# zeeSoC_mp3_Shield_v1_0.net
KiCad netlist of a schematic drawn in EAGLE
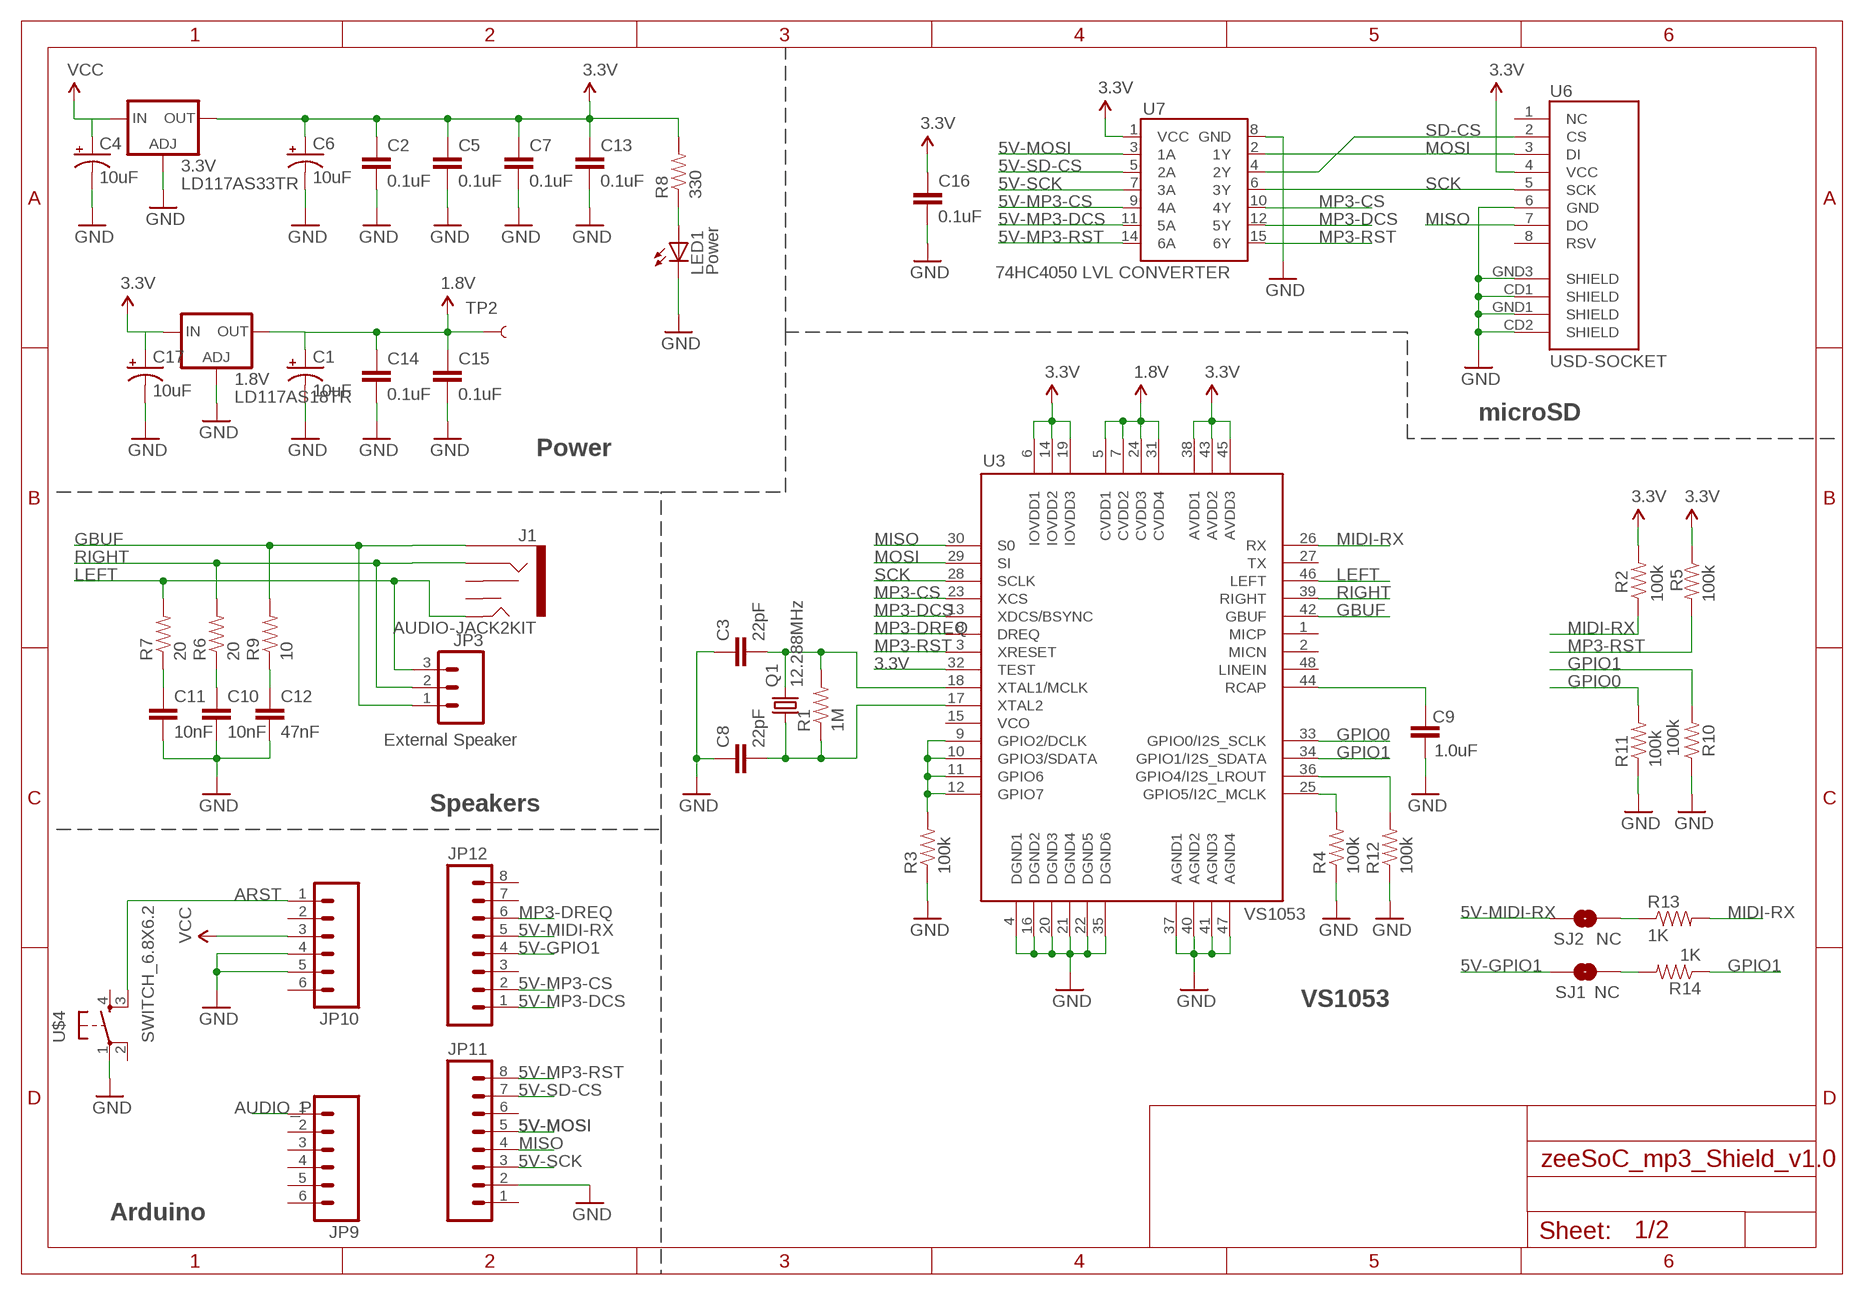
[diagram p0: schematic, sheet 1]
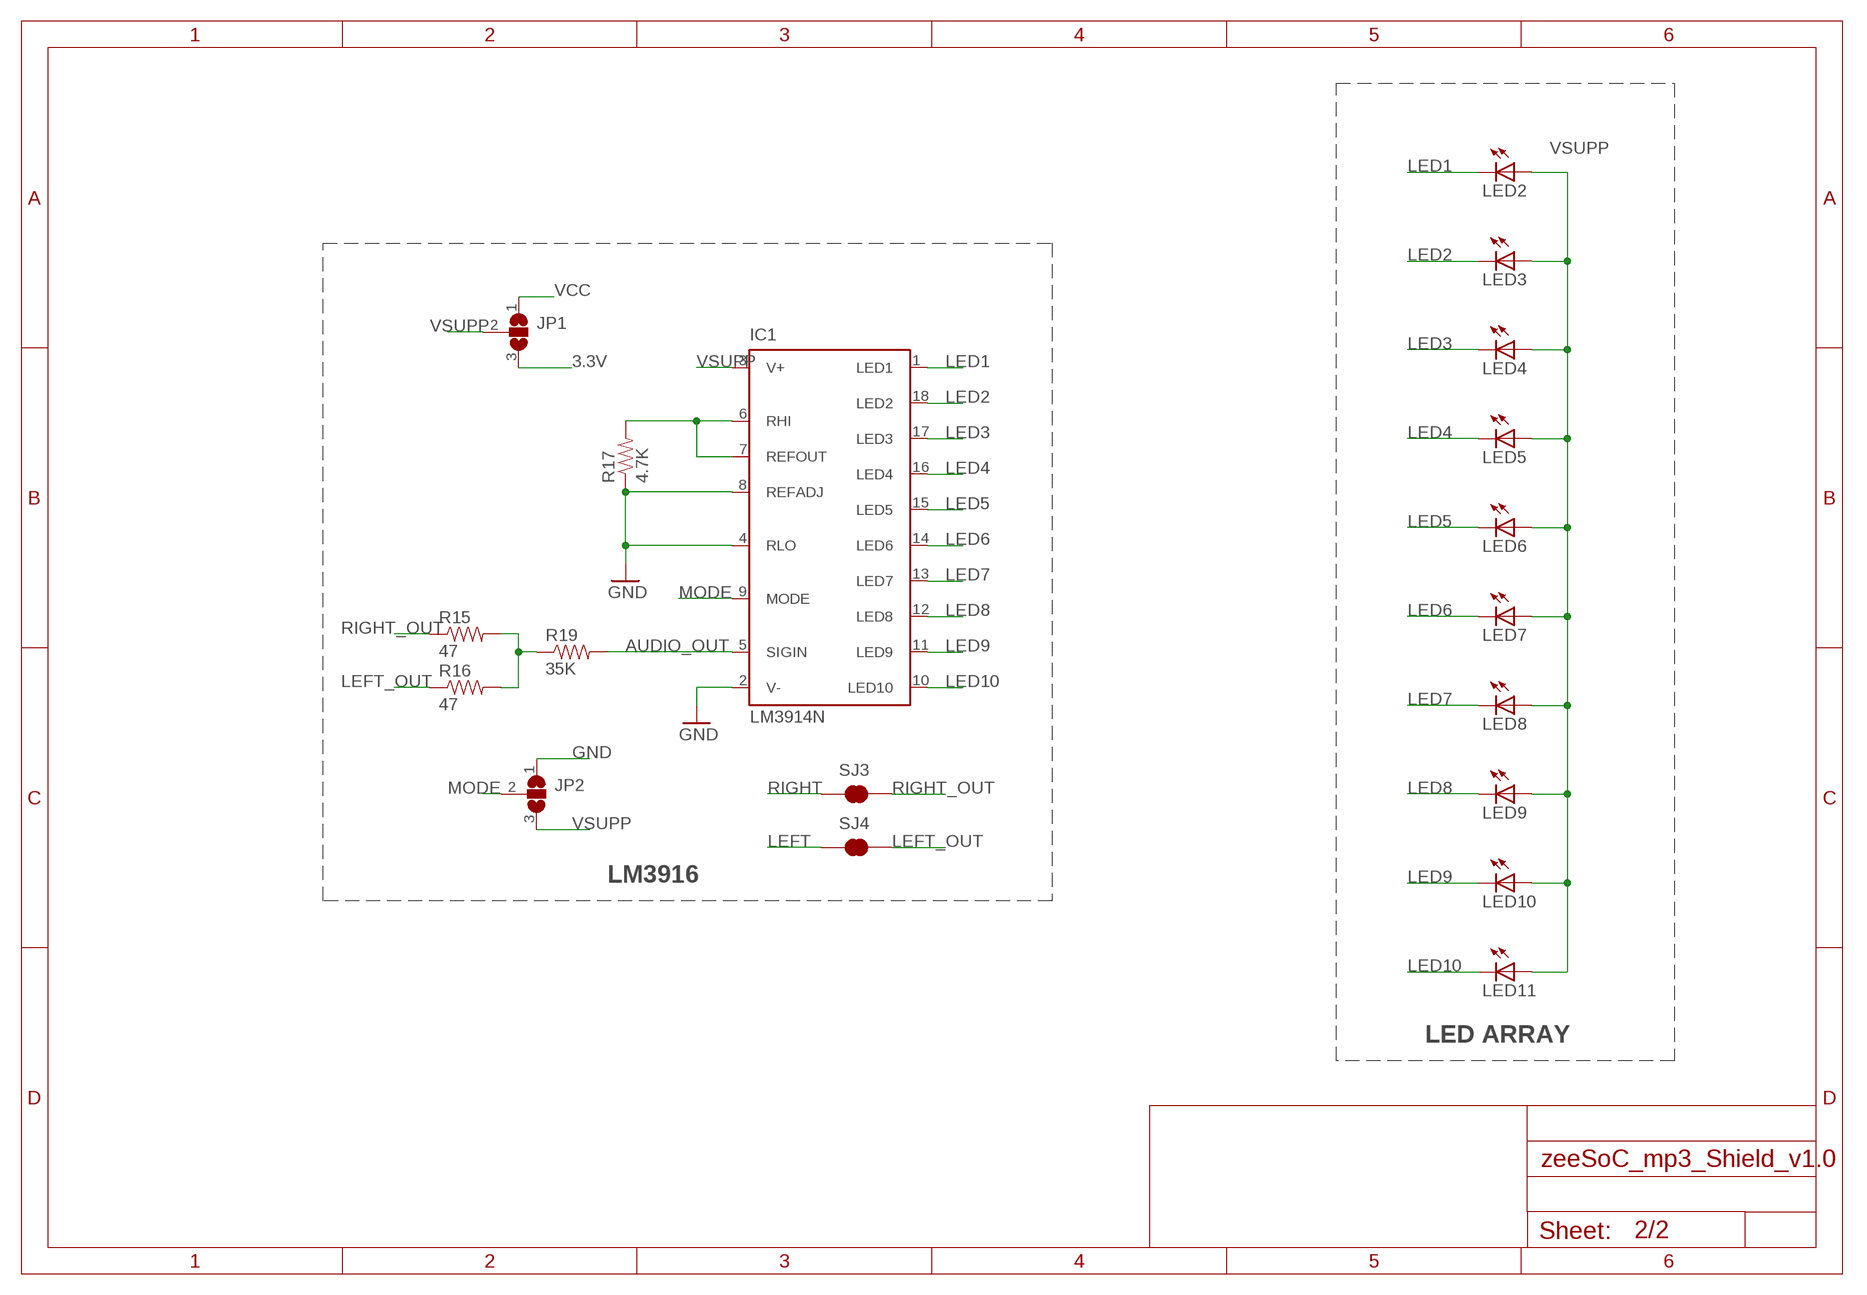
[diagram p1: schematic, sheet 2]

(export (version "E")
  (design (tool "Eeschema 10.0.6"))
  (components
    (comp (ref "1.8V")
      (value "LD117AS18TR")
      (footprint "eagle-import:SOT223")
      (libsource (lib "eagle-import") (part "LD117A?S18TR"))
    )
    (comp (ref "3.3V")
      (value "LD117AS33TR")
      (footprint "eagle-import:SOT223")
      (libsource (lib "eagle-import") (part "LD117A?S33TR"))
    )
    (comp (ref "C1")
      (value "10uF")
      (footprint "eagle-import:EIA3216")
      (libsource (lib "eagle-import") (part "CAP_POL1206"))
    )
    (comp (ref "C2")
      (value "0.1uF")
      (footprint "eagle-import:0603-CAP")
      (libsource (lib "eagle-import") (part "CAP0603-CAP"))
    )
    (comp (ref "C3")
      (value "22pF")
      (footprint "eagle-import:0603-CAP")
      (libsource (lib "eagle-import") (part "CAP0603-CAP"))
    )
    (comp (ref "C4")
      (value "10uF")
      (footprint "eagle-import:EIA3216")
      (libsource (lib "eagle-import") (part "CAP_POL1206"))
    )
    (comp (ref "C5")
      (value "0.1uF")
      (footprint "eagle-import:0603-CAP")
      (libsource (lib "eagle-import") (part "CAP0603-CAP"))
    )
    (comp (ref "C6")
      (value "10uF")
      (footprint "eagle-import:EIA3216")
      (libsource (lib "eagle-import") (part "CAP_POL1206"))
    )
    (comp (ref "C7")
      (value "0.1uF")
      (footprint "eagle-import:0603-CAP")
      (libsource (lib "eagle-import") (part "CAP0603-CAP"))
    )
    (comp (ref "C8")
      (value "22pF")
      (footprint "eagle-import:0603-CAP")
      (libsource (lib "eagle-import") (part "CAP0603-CAP"))
    )
    (comp (ref "C9")
      (value "1.0uF")
      (footprint "eagle-import:0603-CAP")
      (libsource (lib "eagle-import") (part "CAP0603-CAP"))
    )
    (comp (ref "C10")
      (value "10nF")
      (footprint "eagle-import:0603-CAP")
      (libsource (lib "eagle-import") (part "CAP0603-CAP"))
    )
    (comp (ref "C11")
      (value "10nF")
      (footprint "eagle-import:0603-CAP")
      (libsource (lib "eagle-import") (part "CAP0603-CAP"))
    )
    (comp (ref "C12")
      (value "47nF")
      (footprint "eagle-import:0603-CAP")
      (libsource (lib "eagle-import") (part "CAP0603-CAP"))
    )
    (comp (ref "C13")
      (value "0.1uF")
      (footprint "eagle-import:0603-CAP")
      (libsource (lib "eagle-import") (part "CAP0603-CAP"))
    )
    (comp (ref "C14")
      (value "0.1uF")
      (footprint "eagle-import:0603-CAP")
      (libsource (lib "eagle-import") (part "CAP0603-CAP"))
    )
    (comp (ref "C15")
      (value "0.1uF")
      (footprint "eagle-import:0603-CAP")
      (libsource (lib "eagle-import") (part "CAP0603-CAP"))
    )
    (comp (ref "C16")
      (value "0.1uF")
      (footprint "eagle-import:0603-CAP")
      (libsource (lib "eagle-import") (part "CAP0603-CAP"))
    )
    (comp (ref "C17")
      (value "10uF")
      (footprint "eagle-import:EIA3216")
      (libsource (lib "eagle-import") (part "CAP_POL1206"))
    )
    (comp (ref "J1")
      (value "AUDIO-JACK2KIT")
      (footprint "eagle-import:AUDIO-JACK-KIT")
      (libsource (lib "eagle-import") (part "AUDIO-JACK2KIT"))
    )
    (comp (ref "JP3")
      (value "External Speaker")
      (footprint "eagle-import:1X03")
      (libsource (lib "eagle-import") (part "M03PTH"))
    )
    (comp (ref "JP9")
      (value "M06SILK_FEMALE_PTH")
      (footprint "eagle-import:1X06")
      (libsource (lib "eagle-import") (part "M06SILK_FEMALE_PTH"))
    )
    (comp (ref "JP10")
      (value "M06SILK_FEMALE_PTH")
      (footprint "eagle-import:1X06")
      (libsource (lib "eagle-import") (part "M06SILK_FEMALE_PTH"))
    )
    (comp (ref "JP11")
      (value "M08SILK_FEMALE_PTH")
      (footprint "eagle-import:1X08")
      (libsource (lib "eagle-import") (part "M08SILK_FEMALE_PTH"))
    )
    (comp (ref "JP12")
      (value "M08SILK_FEMALE_PTH")
      (footprint "eagle-import:1X08")
      (libsource (lib "eagle-import") (part "M08SILK_FEMALE_PTH"))
    )
    (comp (ref "LED1")
      (value "Power")
      (footprint "eagle-import:LED-0603")
      (libsource (lib "eagle-import") (part "LED0603"))
    )
    (comp (ref "Q1")
      (value "12.288MHz")
      (footprint "eagle-import:HC49US")
      (libsource (lib "eagle-import") (part "CRYSTALHC49US"))
    )
    (comp (ref "R1")
      (value "1M")
      (footprint "eagle-import:0603-RES")
      (libsource (lib "eagle-import") (part "SparkFun-Resistors_RESISTOR0603-RES"))
    )
    (comp (ref "R2")
      (value "100k")
      (footprint "eagle-import:0603-RES")
      (libsource (lib "eagle-import") (part "SparkFun-Resistors_RESISTOR0603-RES"))
    )
    (comp (ref "R3")
      (value "100k")
      (footprint "eagle-import:0603-RES")
      (libsource (lib "eagle-import") (part "SparkFun-Resistors_RESISTOR0603-RES"))
    )
    (comp (ref "R4")
      (value "100k")
      (footprint "eagle-import:0603-RES")
      (libsource (lib "eagle-import") (part "SparkFun-Resistors_RESISTOR0603-RES"))
    )
    (comp (ref "R5")
      (value "100k")
      (footprint "eagle-import:0603-RES")
      (libsource (lib "eagle-import") (part "SparkFun-Resistors_RESISTOR0603-RES"))
    )
    (comp (ref "R6")
      (value "20")
      (footprint "eagle-import:0603-RES")
      (libsource (lib "eagle-import") (part "SparkFun-Resistors_RESISTOR0603-RES"))
    )
    (comp (ref "R7")
      (value "20")
      (footprint "eagle-import:0603-RES")
      (libsource (lib "eagle-import") (part "SparkFun-Resistors_RESISTOR0603-RES"))
    )
    (comp (ref "R8")
      (value "330")
      (footprint "eagle-import:0603-RES")
      (libsource (lib "eagle-import") (part "SparkFun-Resistors_RESISTOR0603-RES"))
    )
    (comp (ref "R9")
      (value "10")
      (footprint "eagle-import:0603-RES")
      (libsource (lib "eagle-import") (part "SparkFun-Resistors_RESISTOR0603-RES"))
    )
    (comp (ref "R10")
      (value "100k")
      (footprint "eagle-import:0603-RES")
      (libsource (lib "eagle-import") (part "RESISTOR0603-RES"))
    )
    (comp (ref "R11")
      (value "100k")
      (footprint "eagle-import:0603-RES")
      (libsource (lib "eagle-import") (part "RESISTOR0603-RES"))
    )
    (comp (ref "R12")
      (value "100k")
      (footprint "eagle-import:0603-RES")
      (libsource (lib "eagle-import") (part "SparkFun-Resistors_RESISTOR0603-RES"))
    )
    (comp (ref "R13")
      (value "1K")
      (footprint "eagle-import:0603-RES")
      (libsource (lib "eagle-import") (part "SparkFun-Resistors_RESISTOR0603-RES"))
    )
    (comp (ref "R14")
      (value "1K")
      (footprint "eagle-import:0603-RES")
      (libsource (lib "eagle-import") (part "SparkFun-Resistors_RESISTOR0603-RES"))
    )
    (comp (ref "SJ1")
      (value "NC")
      (footprint "eagle-import:PAD-JUMPER-2-NO_YES_SILK")
      (libsource (lib "eagle-import") (part "JUMPER-PAD-2-NOYES_SILK"))
    )
    (comp (ref "SJ2")
      (value "NC")
      (footprint "eagle-import:PAD-JUMPER-2-NO_YES_SILK")
      (libsource (lib "eagle-import") (part "JUMPER-PAD-2-NOYES_SILK"))
    )
    (comp (ref "TP2")
      (value "TEST-POINT3X5")
      (footprint "eagle-import:PAD.03X.05")
      (libsource (lib "eagle-import") (part "TEST-POINT3X5"))
    )
    (comp (ref "U$4")
      (value "SWITCH_6.8X6.2")
      (footprint "eagle-import:SWITCH_6.8X6.2")
      (libsource (lib "eagle-import") (part "SWITCH_6.8X6.2"))
    )
    (comp (ref "U3")
      (value "VS1053")
      (footprint "eagle-import:LQFP-48")
      (libsource (lib "eagle-import") (part "VS1033"))
    )
    (comp (ref "U6")
      (value "USD-SOCKET")
      (footprint "eagle-import:MICRO-SD-SOCKET-PP")
      (libsource (lib "eagle-import") (part "USD-SOCKETNEW"))
    )
    (comp (ref "U7")
      (value "74HC4050 LVL CONVERTER")
      (footprint "eagle-import:SO016")
      (libsource (lib "eagle-import") (part "HEX_CONVERTER"))
    )
    (comp (ref "IC1")
      (value "LM3914N")
      (footprint "eagle-import:DIL18")
      (libsource (lib "eagle-import") (part "LM391N4"))
    )
    (comp (ref "JP1")
      (value "SJ2W")
      (footprint "eagle-import:SJ_2")
      (libsource (lib "eagle-import") (part "SJ2W"))
    )
    (comp (ref "JP2")
      (value "SJ2W")
      (footprint "eagle-import:SJ_2")
      (libsource (lib "eagle-import") (part "SJ2W"))
    )
    (comp (ref "LED2")
      (value "LEDCHIPLED_0603")
      (footprint "eagle-import:CHIPLED_0603")
      (libsource (lib "eagle-import") (part "LEDCHIPLED_0603"))
    )
    (comp (ref "LED3")
      (value "LEDCHIPLED_0603")
      (footprint "eagle-import:CHIPLED_0603")
      (libsource (lib "eagle-import") (part "LEDCHIPLED_0603"))
    )
    (comp (ref "LED4")
      (value "LEDCHIPLED_0603")
      (footprint "eagle-import:CHIPLED_0603")
      (libsource (lib "eagle-import") (part "LEDCHIPLED_0603"))
    )
    (comp (ref "LED5")
      (value "LEDCHIPLED_0603")
      (footprint "eagle-import:CHIPLED_0603")
      (libsource (lib "eagle-import") (part "LEDCHIPLED_0603"))
    )
    (comp (ref "LED6")
      (value "LEDCHIPLED_0603")
      (footprint "eagle-import:CHIPLED_0603")
      (libsource (lib "eagle-import") (part "LEDCHIPLED_0603"))
    )
    (comp (ref "LED7")
      (value "LEDCHIPLED_0603")
      (footprint "eagle-import:CHIPLED_0603")
      (libsource (lib "eagle-import") (part "LEDCHIPLED_0603"))
    )
    (comp (ref "LED8")
      (value "LEDCHIPLED_0603")
      (footprint "eagle-import:CHIPLED_0603")
      (libsource (lib "eagle-import") (part "LEDCHIPLED_0603"))
    )
    (comp (ref "LED9")
      (value "LEDCHIPLED_0603")
      (footprint "eagle-import:CHIPLED_0603")
      (libsource (lib "eagle-import") (part "LEDCHIPLED_0603"))
    )
    (comp (ref "LED10")
      (value "LEDCHIPLED_0603")
      (footprint "eagle-import:CHIPLED_0603")
      (libsource (lib "eagle-import") (part "LEDCHIPLED_0603"))
    )
    (comp (ref "LED11")
      (value "LEDCHIPLED_0603")
      (footprint "eagle-import:CHIPLED_0603")
      (libsource (lib "eagle-import") (part "LEDCHIPLED_0603"))
    )
    (comp (ref "R15")
      (value "47")
      (footprint "eagle-import:0603-RES")
      (libsource (lib "eagle-import") (part "SparkFun-Resistors_RESISTOR0603-RES"))
    )
    (comp (ref "R16")
      (value "47")
      (footprint "eagle-import:0603-RES")
      (libsource (lib "eagle-import") (part "SparkFun-Resistors_RESISTOR0603-RES"))
    )
    (comp (ref "R17")
      (value "4.7K")
      (footprint "eagle-import:0603-RES")
      (libsource (lib "eagle-import") (part "SparkFun-Resistors_RESISTOR0603-RES"))
    )
    (comp (ref "R19")
      (value "35K")
      (footprint "eagle-import:0603-RES")
      (libsource (lib "eagle-import") (part "SparkFun-Resistors_RESISTOR0603-RES"))
    )
    (comp (ref "SJ3")
      (value "JUMPER-PAD-2-NC_BY_TRACE")
      (footprint "eagle-import:PAD-JUMPER-2-NC_BY_TRACE_YES_SILK")
      (libsource (lib "eagle-import") (part "JUMPER-PAD-2-NC_BY_TRACE"))
    )
    (comp (ref "SJ4")
      (value "JUMPER-PAD-2-NC_BY_TRACE")
      (footprint "eagle-import:PAD-JUMPER-2-NC_BY_TRACE_YES_SILK")
      (libsource (lib "eagle-import") (part "JUMPER-PAD-2-NC_BY_TRACE"))
    )
  )
  (nets
    (net (code "1") (name "1.8V") (class "Default")
      (node (ref "1.8V") (pin "4") (pinfunction "OUT_4") (pintype "passive"))
      (node (ref "C1") (pin "A") (pinfunction "+_A") (pintype "passive"))
      (node (ref "C14") (pin "1") (pinfunction "1_1") (pintype "passive"))
      (node (ref "C15") (pin "1") (pinfunction "1_1") (pintype "passive"))
      (node (ref "TP2") (pin "P$1") (pinfunction "1_P$1") (pintype "bidirectional"))
      (node (ref "U3") (pin "24") (pinfunction "CVDD3_24") (pintype "bidirectional"))
      (node (ref "U3") (pin "31") (pinfunction "CVDD4_31") (pintype "bidirectional"))
      (node (ref "U3") (pin "5") (pinfunction "CVDD1_5") (pintype "bidirectional"))
      (node (ref "U3") (pin "7") (pinfunction "CVDD2_7") (pintype "bidirectional"))
    )
    (net (code "2") (name "3.3V") (class "Default")
      (node (ref "1.8V") (pin "3") (pinfunction "IN_3") (pintype "input"))
      (node (ref "3.3V") (pin "4") (pinfunction "OUT_4") (pintype "passive"))
      (node (ref "C13") (pin "1") (pinfunction "1_1") (pintype "passive"))
      (node (ref "C16") (pin "1") (pinfunction "1_1") (pintype "passive"))
      (node (ref "C17") (pin "A") (pinfunction "+_A") (pintype "passive"))
      (node (ref "C2") (pin "1") (pinfunction "1_1") (pintype "passive"))
      (node (ref "C5") (pin "1") (pinfunction "1_1") (pintype "passive"))
      (node (ref "C6") (pin "A") (pinfunction "+_A") (pintype "passive"))
      (node (ref "C7") (pin "1") (pinfunction "1_1") (pintype "passive"))
      (node (ref "JP1") (pin "1") (pinfunction "1_1") (pintype "passive"))
      (node (ref "R2") (pin "2") (pinfunction "2_2") (pintype "passive"))
      (node (ref "R5") (pin "1") (pinfunction "1_1") (pintype "passive"))
      (node (ref "R8") (pin "2") (pinfunction "2_2") (pintype "passive"))
      (node (ref "U3") (pin "14") (pinfunction "IOVDD2_14") (pintype "bidirectional"))
      (node (ref "U3") (pin "19") (pinfunction "IOVDD3_19") (pintype "bidirectional"))
      (node (ref "U3") (pin "32") (pinfunction "TEST_32") (pintype "bidirectional"))
      (node (ref "U3") (pin "38") (pinfunction "AVDD1_38") (pintype "bidirectional"))
      (node (ref "U3") (pin "43") (pinfunction "AVDD2_43") (pintype "bidirectional"))
      (node (ref "U3") (pin "45") (pinfunction "AVDD3_45") (pintype "bidirectional"))
      (node (ref "U3") (pin "6") (pinfunction "IOVDD1_6") (pintype "bidirectional"))
      (node (ref "U6") (pin "4") (pinfunction "VCC_4") (pintype "bidirectional"))
      (node (ref "U7") (pin "1") (pinfunction "VCC_1") (pintype "bidirectional"))
    )
    (net (code "3") (name "5V-GPIO1") (class "Default")
      (node (ref "JP12") (pin "4") (pinfunction "4_4") (pintype "passive"))
      (node (ref "SJ1") (pin "2") (pinfunction "2_2") (pintype "passive"))
    )
    (net (code "4") (name "5V-MIDI-RX") (class "Default")
      (node (ref "JP12") (pin "5") (pinfunction "5_5") (pintype "passive"))
      (node (ref "SJ2") (pin "1") (pinfunction "1_1") (pintype "passive"))
    )
    (net (code "5") (name "5V-MOSI") (class "Default")
      (node (ref "JP11") (pin "5") (pinfunction "5_5") (pintype "passive"))
      (node (ref "U7") (pin "3") (pinfunction "1A_3") (pintype "bidirectional"))
    )
    (net (code "6") (name "5V-MP3-CS") (class "Default")
      (node (ref "JP12") (pin "2") (pinfunction "2_2") (pintype "passive"))
      (node (ref "U7") (pin "9") (pinfunction "4A_9") (pintype "bidirectional"))
    )
    (net (code "7") (name "5V-MP3-DCS") (class "Default")
      (node (ref "JP12") (pin "1") (pinfunction "1_1") (pintype "passive"))
      (node (ref "U7") (pin "11") (pinfunction "5A_11") (pintype "bidirectional"))
    )
    (net (code "8") (name "5V-MP3-RST") (class "Default")
      (node (ref "JP11") (pin "8") (pinfunction "8_8") (pintype "passive"))
      (node (ref "U7") (pin "14") (pinfunction "6A_14") (pintype "bidirectional"))
    )
    (net (code "9") (name "5V-SCK") (class "Default")
      (node (ref "JP11") (pin "3") (pinfunction "3_3") (pintype "passive"))
      (node (ref "U7") (pin "7") (pinfunction "3A_7") (pintype "bidirectional"))
    )
    (net (code "10") (name "5V-SD-CS") (class "Default")
      (node (ref "JP11") (pin "7") (pinfunction "7_7") (pintype "passive"))
      (node (ref "U7") (pin "5") (pinfunction "2A_5") (pintype "bidirectional"))
    )
    (net (code "11") (name "ARST") (class "Default")
      (node (ref "JP10") (pin "1") (pinfunction "1_1") (pintype "passive"))
      (node (ref "U$4") (pin "3") (pinfunction "3_3") (pintype "passive"))
    )
    (net (code "12") (name "AUDIO_OUT") (class "Default")
      (node (ref "IC1") (pin "5") (pinfunction "SIGIN_5") (pintype "input"))
      (node (ref "R19") (pin "2") (pinfunction "2_2") (pintype "passive"))
    )
    (net (code "13") (name "AUDIO_P") (class "Default")
      (node (ref "JP9") (pin "1") (pinfunction "1_1") (pintype "passive"))
    )
    (net (code "14") (name "GBUF") (class "Default")
      (node (ref "J1") (pin "SLEEVE") (pinfunction "SLEEVE_SLEEVE") (pintype "bidirectional"))
      (node (ref "JP3") (pin "1") (pinfunction "1_1") (pintype "passive"))
      (node (ref "R9") (pin "2") (pinfunction "2_2") (pintype "passive"))
      (node (ref "U3") (pin "42") (pinfunction "GBUF_42") (pintype "bidirectional"))
    )
    (net (code "15") (name "GND") (class "Default")
      (node (ref "1.8V") (pin "1") (pinfunction "ADJ_1") (pintype "input"))
      (node (ref "3.3V") (pin "1") (pinfunction "ADJ_1") (pintype "input"))
      (node (ref "C1") (pin "C") (pinfunction "-_C") (pintype "passive"))
      (node (ref "C10") (pin "2") (pinfunction "2_2") (pintype "passive"))
      (node (ref "C11") (pin "2") (pinfunction "2_2") (pintype "passive"))
      (node (ref "C12") (pin "2") (pinfunction "2_2") (pintype "passive"))
      (node (ref "C13") (pin "2") (pinfunction "2_2") (pintype "passive"))
      (node (ref "C14") (pin "2") (pinfunction "2_2") (pintype "passive"))
      (node (ref "C15") (pin "2") (pinfunction "2_2") (pintype "passive"))
      (node (ref "C16") (pin "2") (pinfunction "2_2") (pintype "passive"))
      (node (ref "C17") (pin "C") (pinfunction "-_C") (pintype "passive"))
      (node (ref "C2") (pin "2") (pinfunction "2_2") (pintype "passive"))
      (node (ref "C3") (pin "1") (pinfunction "1_1") (pintype "passive"))
      (node (ref "C4") (pin "C") (pinfunction "-_C") (pintype "passive"))
      (node (ref "C5") (pin "2") (pinfunction "2_2") (pintype "passive"))
      (node (ref "C6") (pin "C") (pinfunction "-_C") (pintype "passive"))
      (node (ref "C7") (pin "2") (pinfunction "2_2") (pintype "passive"))
      (node (ref "C8") (pin "1") (pinfunction "1_1") (pintype "passive"))
      (node (ref "C9") (pin "1") (pinfunction "1_1") (pintype "passive"))
      (node (ref "IC1") (pin "2") (pinfunction "V-_2") (pintype "power_in"))
      (node (ref "IC1") (pin "4") (pinfunction "RLO_4") (pintype "input"))
      (node (ref "IC1") (pin "8") (pinfunction "REFADJ_8") (pintype "passive"))
      (node (ref "JP10") (pin "4") (pinfunction "4_4") (pintype "passive"))
      (node (ref "JP10") (pin "5") (pinfunction "5_5") (pintype "passive"))
      (node (ref "JP11") (pin "2") (pinfunction "2_2") (pintype "passive"))
      (node (ref "JP2") (pin "1") (pinfunction "1_1") (pintype "passive"))
      (node (ref "LED1") (pin "C") (pinfunction "C_C") (pintype "passive"))
      (node (ref "R10") (pin "1") (pinfunction "1_1") (pintype "passive"))
      (node (ref "R11") (pin "1") (pinfunction "1_1") (pintype "passive"))
      (node (ref "R12") (pin "1") (pinfunction "1_1") (pintype "passive"))
      (node (ref "R17") (pin "1") (pinfunction "1_1") (pintype "passive"))
      (node (ref "R3") (pin "1") (pinfunction "1_1") (pintype "passive"))
      (node (ref "R4") (pin "1") (pinfunction "1_1") (pintype "passive"))
      (node (ref "U$4") (pin "1") (pinfunction "1_1") (pintype "passive"))
      (node (ref "U3") (pin "16") (pinfunction "DGND2_16") (pintype "bidirectional"))
      (node (ref "U3") (pin "20") (pinfunction "DGND3_20") (pintype "bidirectional"))
      (node (ref "U3") (pin "21") (pinfunction "DGND4_21") (pintype "bidirectional"))
      (node (ref "U3") (pin "22") (pinfunction "DGND5_22") (pintype "bidirectional"))
      (node (ref "U3") (pin "35") (pinfunction "DGND6_35") (pintype "bidirectional"))
      (node (ref "U3") (pin "37") (pinfunction "AGND1_37") (pintype "bidirectional"))
      (node (ref "U3") (pin "4") (pinfunction "DGND1_4") (pintype "bidirectional"))
      (node (ref "U3") (pin "40") (pinfunction "AGND2_40") (pintype "bidirectional"))
      (node (ref "U3") (pin "41") (pinfunction "AGND3_41") (pintype "bidirectional"))
      (node (ref "U3") (pin "47") (pinfunction "AGND4_47") (pintype "bidirectional"))
      (node (ref "U6") (pin "6") (pinfunction "GND_6") (pintype "bidirectional"))
      (node (ref "U6") (pin "CD1") (pinfunction "SHIELD_CD1") (pintype "bidirectional"))
      (node (ref "U6") (pin "CD2") (pinfunction "SHIELD_CD2") (pintype "bidirectional"))
      (node (ref "U6") (pin "GND1") (pinfunction "SHIELD_GND1") (pintype "bidirectional"))
      (node (ref "U6") (pin "GND3") (pinfunction "SHIELD_GND3") (pintype "bidirectional"))
      (node (ref "U7") (pin "8") (pinfunction "GND_8") (pintype "bidirectional"))
    )
    (net (code "16") (name "GPIO0") (class "Default")
      (node (ref "R11") (pin "2") (pinfunction "2_2") (pintype "passive"))
      (node (ref "U3") (pin "33") (pinfunction "GPIO0/I2S_SCLK_33") (pintype "bidirectional"))
    )
    (net (code "17") (name "GPIO1") (class "Default")
      (node (ref "R10") (pin "2") (pinfunction "2_2") (pintype "passive"))
      (node (ref "R14") (pin "1") (pinfunction "1_1") (pintype "passive"))
      (node (ref "U3") (pin "34") (pinfunction "GPIO1/I2S_SDATA_34") (pintype "bidirectional"))
    )
    (net (code "18") (name "LED1") (class "Default")
      (node (ref "IC1") (pin "1") (pinfunction "LED1_1") (pintype "output"))
      (node (ref "LED2") (pin "C") (pinfunction "C_C") (pintype "passive"))
    )
    (net (code "19") (name "LED2") (class "Default")
      (node (ref "IC1") (pin "18") (pinfunction "LED2_18") (pintype "output"))
      (node (ref "LED3") (pin "C") (pinfunction "C_C") (pintype "passive"))
    )
    (net (code "20") (name "LED3") (class "Default")
      (node (ref "IC1") (pin "17") (pinfunction "LED3_17") (pintype "output"))
      (node (ref "LED4") (pin "C") (pinfunction "C_C") (pintype "passive"))
    )
    (net (code "21") (name "LED4") (class "Default")
      (node (ref "IC1") (pin "16") (pinfunction "LED4_16") (pintype "output"))
      (node (ref "LED5") (pin "C") (pinfunction "C_C") (pintype "passive"))
    )
    (net (code "22") (name "LED5") (class "Default")
      (node (ref "IC1") (pin "15") (pinfunction "LED5_15") (pintype "output"))
      (node (ref "LED6") (pin "C") (pinfunction "C_C") (pintype "passive"))
    )
    (net (code "23") (name "LED6") (class "Default")
      (node (ref "IC1") (pin "14") (pinfunction "LED6_14") (pintype "output"))
      (node (ref "LED7") (pin "C") (pinfunction "C_C") (pintype "passive"))
    )
    (net (code "24") (name "LED7") (class "Default")
      (node (ref "IC1") (pin "13") (pinfunction "LED7_13") (pintype "output"))
      (node (ref "LED8") (pin "C") (pinfunction "C_C") (pintype "passive"))
    )
    (net (code "25") (name "LED8") (class "Default")
      (node (ref "IC1") (pin "12") (pinfunction "LED8_12") (pintype "output"))
      (node (ref "LED9") (pin "C") (pinfunction "C_C") (pintype "passive"))
    )
    (net (code "26") (name "LED9") (class "Default")
      (node (ref "IC1") (pin "11") (pinfunction "LED9_11") (pintype "output"))
      (node (ref "LED10") (pin "C") (pinfunction "C_C") (pintype "passive"))
    )
    (net (code "27") (name "LED10") (class "Default")
      (node (ref "IC1") (pin "10") (pinfunction "LED10_10") (pintype "output"))
      (node (ref "LED11") (pin "C") (pinfunction "C_C") (pintype "passive"))
    )
    (net (code "28") (name "LEFT") (class "Default")
      (node (ref "J1") (pin "TIP") (pinfunction "TIP_TIP") (pintype "bidirectional"))
      (node (ref "JP3") (pin "3") (pinfunction "3_3") (pintype "passive"))
      (node (ref "R7") (pin "2") (pinfunction "2_2") (pintype "passive"))
      (node (ref "SJ4") (pin "1") (pinfunction "1_1") (pintype "passive"))
      (node (ref "U3") (pin "46") (pinfunction "LEFT_46") (pintype "bidirectional"))
    )
    (net (code "29") (name "LEFT_OUT") (class "Default")
      (node (ref "R16") (pin "1") (pinfunction "1_1") (pintype "passive"))
      (node (ref "SJ4") (pin "2") (pinfunction "2_2") (pintype "passive"))
    )
    (net (code "30") (name "MIDI-RX") (class "Default")
      (node (ref "R13") (pin "2") (pinfunction "2_2") (pintype "passive"))
      (node (ref "R2") (pin "1") (pinfunction "1_1") (pintype "passive"))
      (node (ref "U3") (pin "26") (pinfunction "RX_26") (pintype "bidirectional"))
    )
    (net (code "31") (name "MISO") (class "Default")
      (node (ref "JP11") (pin "4") (pinfunction "4_4") (pintype "passive"))
      (node (ref "U3") (pin "30") (pinfunction "S0_30") (pintype "bidirectional"))
      (node (ref "U6") (pin "7") (pinfunction "DO_7") (pintype "bidirectional"))
    )
    (net (code "32") (name "MODE") (class "Default")
      (node (ref "IC1") (pin "9") (pinfunction "MODE_9") (pintype "input"))
      (node (ref "JP2") (pin "2") (pinfunction "2_2") (pintype "passive"))
    )
    (net (code "33") (name "MOSI") (class "Default")
      (node (ref "U3") (pin "29") (pinfunction "SI_29") (pintype "bidirectional"))
      (node (ref "U6") (pin "3") (pinfunction "DI_3") (pintype "bidirectional"))
      (node (ref "U7") (pin "2") (pinfunction "1Y_2") (pintype "bidirectional"))
    )
    (net (code "34") (name "MP3-CS") (class "Default")
      (node (ref "U3") (pin "23") (pinfunction "XCS_23") (pintype "bidirectional"))
      (node (ref "U7") (pin "10") (pinfunction "4Y_10") (pintype "bidirectional"))
    )
    (net (code "35") (name "MP3-DCS") (class "Default")
      (node (ref "U3") (pin "13") (pinfunction "XDCS/BSYNC_13") (pintype "bidirectional"))
      (node (ref "U7") (pin "12") (pinfunction "5Y_12") (pintype "bidirectional"))
    )
    (net (code "36") (name "MP3-DREQ") (class "Default")
      (node (ref "JP12") (pin "6") (pinfunction "6_6") (pintype "passive"))
      (node (ref "U3") (pin "8") (pinfunction "DREQ_8") (pintype "bidirectional"))
    )
    (net (code "37") (name "MP3-RST") (class "Default")
      (node (ref "R5") (pin "2") (pinfunction "2_2") (pintype "passive"))
      (node (ref "U3") (pin "3") (pinfunction "XRESET_3") (pintype "bidirectional"))
      (node (ref "U7") (pin "15") (pinfunction "6Y_15") (pintype "bidirectional"))
    )
    (net (code "38") (name "Net-(C10-Pad1)") (class "Default")
      (node (ref "C10") (pin "1") (pinfunction "1_1") (pintype "passive"))
      (node (ref "R6") (pin "1") (pinfunction "1_1") (pintype "passive"))
    )
    (net (code "39") (name "Net-(C11-Pad1)") (class "Default")
      (node (ref "C11") (pin "1") (pinfunction "1_1") (pintype "passive"))
      (node (ref "R7") (pin "1") (pinfunction "1_1") (pintype "passive"))
    )
    (net (code "40") (name "Net-(C12-Pad1)") (class "Default")
      (node (ref "C12") (pin "1") (pinfunction "1_1") (pintype "passive"))
      (node (ref "R9") (pin "1") (pinfunction "1_1") (pintype "passive"))
    )
    (net (code "41") (name "Net-(IC1-REFOUT)") (class "Default")
      (node (ref "IC1") (pin "6") (pinfunction "RHI_6") (pintype "input"))
      (node (ref "IC1") (pin "7") (pinfunction "REFOUT_7") (pintype "output"))
      (node (ref "R17") (pin "2") (pinfunction "2_2") (pintype "passive"))
    )
    (net (code "42") (name "Net-(LED1-PadA)") (class "Default")
      (node (ref "LED1") (pin "A") (pinfunction "A_A") (pintype "passive"))
      (node (ref "R8") (pin "1") (pinfunction "1_1") (pintype "passive"))
    )
    (net (code "43") (name "Net-(R13-Pad1)") (class "Default")
      (node (ref "R13") (pin "1") (pinfunction "1_1") (pintype "passive"))
      (node (ref "SJ2") (pin "2") (pinfunction "2_2") (pintype "passive"))
    )
    (net (code "44") (name "Net-(R14-Pad2)") (class "Default")
      (node (ref "R14") (pin "2") (pinfunction "2_2") (pintype "passive"))
      (node (ref "SJ1") (pin "1") (pinfunction "1_1") (pintype "passive"))
    )
    (net (code "45") (name "Net-(R15-Pad2)") (class "Default")
      (node (ref "R15") (pin "2") (pinfunction "2_2") (pintype "passive"))
      (node (ref "R16") (pin "2") (pinfunction "2_2") (pintype "passive"))
      (node (ref "R19") (pin "1") (pinfunction "1_1") (pintype "passive"))
    )
    (net (code "46") (name "Net-(U3-GPIO2{slash}DCLK)") (class "Default")
      (node (ref "R3") (pin "2") (pinfunction "2_2") (pintype "passive"))
      (node (ref "U3") (pin "10") (pinfunction "GPIO3/SDATA_10") (pintype "bidirectional"))
      (node (ref "U3") (pin "11") (pinfunction "GPIO6_11") (pintype "bidirectional"))
      (node (ref "U3") (pin "12") (pinfunction "GPIO7_12") (pintype "bidirectional"))
      (node (ref "U3") (pin "9") (pinfunction "GPIO2/DCLK_9") (pintype "bidirectional"))
    )
    (net (code "47") (name "Net-(U3-GPIO4{slash}I2S_LROUT)") (class "Default")
      (node (ref "R12") (pin "2") (pinfunction "2_2") (pintype "passive"))
      (node (ref "U3") (pin "36") (pinfunction "GPIO4/I2S_LROUT_36") (pintype "bidirectional"))
    )
    (net (code "48") (name "Net-(U3-GPIO5{slash}I2C_MCLK)") (class "Default")
      (node (ref "R4") (pin "2") (pinfunction "2_2") (pintype "passive"))
      (node (ref "U3") (pin "25") (pinfunction "GPIO5/I2C_MCLK_25") (pintype "bidirectional"))
    )
    (net (code "49") (name "Net-(U3-RCAP)") (class "Default")
      (node (ref "C9") (pin "2") (pinfunction "2_2") (pintype "passive"))
      (node (ref "U3") (pin "44") (pinfunction "RCAP_44") (pintype "bidirectional"))
    )
    (net (code "50") (name "Net-(U3-XTAL1{slash}MCLK)") (class "Default")
      (node (ref "C3") (pin "2") (pinfunction "2_2") (pintype "passive"))
      (node (ref "Q1") (pin "2") (pinfunction "2_2") (pintype "passive"))
      (node (ref "R1") (pin "2") (pinfunction "2_2") (pintype "passive"))
      (node (ref "U3") (pin "18") (pinfunction "XTAL1/MCLK_18") (pintype "bidirectional"))
    )
    (net (code "51") (name "Net-(U3-XTAL2)") (class "Default")
      (node (ref "C8") (pin "2") (pinfunction "2_2") (pintype "passive"))
      (node (ref "Q1") (pin "1") (pinfunction "1_1") (pintype "passive"))
      (node (ref "R1") (pin "1") (pinfunction "1_1") (pintype "passive"))
      (node (ref "U3") (pin "17") (pinfunction "XTAL2_17") (pintype "bidirectional"))
    )
    (net (code "52") (name "RIGHT") (class "Default")
      (node (ref "J1") (pin "RING") (pinfunction "RING_RING") (pintype "bidirectional"))
      (node (ref "JP3") (pin "2") (pinfunction "2_2") (pintype "passive"))
      (node (ref "R6") (pin "2") (pinfunction "2_2") (pintype "passive"))
      (node (ref "SJ3") (pin "1") (pinfunction "1_1") (pintype "passive"))
      (node (ref "U3") (pin "39") (pinfunction "RIGHT_39") (pintype "bidirectional"))
    )
    (net (code "53") (name "RIGHT_OUT") (class "Default")
      (node (ref "R15") (pin "1") (pinfunction "1_1") (pintype "passive"))
      (node (ref "SJ3") (pin "2") (pinfunction "2_2") (pintype "passive"))
    )
    (net (code "54") (name "SCK") (class "Default")
      (node (ref "U3") (pin "28") (pinfunction "SCLK_28") (pintype "bidirectional"))
      (node (ref "U6") (pin "5") (pinfunction "SCK_5") (pintype "bidirectional"))
      (node (ref "U7") (pin "6") (pinfunction "3Y_6") (pintype "bidirectional"))
    )
    (net (code "55") (name "SD-CS") (class "Default")
      (node (ref "U6") (pin "2") (pinfunction "CS_2") (pintype "bidirectional"))
      (node (ref "U7") (pin "4") (pinfunction "2Y_4") (pintype "bidirectional"))
    )
    (net (code "56") (name "VCC") (class "Default")
      (node (ref "3.3V") (pin "3") (pinfunction "IN_3") (pintype "input"))
      (node (ref "C4") (pin "A") (pinfunction "+_A") (pintype "passive"))
      (node (ref "JP1") (pin "3") (pinfunction "3_3") (pintype "passive"))
      (node (ref "JP10") (pin "3") (pinfunction "3_3") (pintype "passive"))
    )
    (net (code "57") (name "VSUPP") (class "Default")
      (node (ref "IC1") (pin "3") (pinfunction "V+_3") (pintype "power_in"))
      (node (ref "JP1") (pin "2") (pinfunction "2_2") (pintype "passive"))
      (node (ref "JP2") (pin "3") (pinfunction "3_3") (pintype "passive"))
      (node (ref "LED10") (pin "A") (pinfunction "A_A") (pintype "passive"))
      (node (ref "LED11") (pin "A") (pinfunction "A_A") (pintype "passive"))
      (node (ref "LED2") (pin "A") (pinfunction "A_A") (pintype "passive"))
      (node (ref "LED3") (pin "A") (pinfunction "A_A") (pintype "passive"))
      (node (ref "LED4") (pin "A") (pinfunction "A_A") (pintype "passive"))
      (node (ref "LED5") (pin "A") (pinfunction "A_A") (pintype "passive"))
      (node (ref "LED6") (pin "A") (pinfunction "A_A") (pintype "passive"))
      (node (ref "LED7") (pin "A") (pinfunction "A_A") (pintype "passive"))
      (node (ref "LED8") (pin "A") (pinfunction "A_A") (pintype "passive"))
      (node (ref "LED9") (pin "A") (pinfunction "A_A") (pintype "passive"))
    )
    (net (code "58") (name "unconnected-(J1-PadRSH)") (class "Default")
      (node (ref "J1") (pin "RSH") (pinfunction "RSH_RSH") (pintype "bidirectional"))
    )
    (net (code "59") (name "unconnected-(J1-PadTSH)") (class "Default")
      (node (ref "J1") (pin "TSH") (pinfunction "TSH_TSH") (pintype "bidirectional"))
    )
    (net (code "60") (name "unconnected-(JP9-Pad2)") (class "Default")
      (node (ref "JP9") (pin "2") (pinfunction "2_2") (pintype "passive"))
    )
    (net (code "61") (name "unconnected-(JP9-Pad3)") (class "Default")
      (node (ref "JP9") (pin "3") (pinfunction "3_3") (pintype "passive"))
    )
    (net (code "62") (name "unconnected-(JP9-Pad4)") (class "Default")
      (node (ref "JP9") (pin "4") (pinfunction "4_4") (pintype "passive"))
    )
    (net (code "63") (name "unconnected-(JP9-Pad5)") (class "Default")
      (node (ref "JP9") (pin "5") (pinfunction "5_5") (pintype "passive"))
    )
    (net (code "64") (name "unconnected-(JP9-Pad6)") (class "Default")
      (node (ref "JP9") (pin "6") (pinfunction "6_6") (pintype "passive"))
    )
    (net (code "65") (name "unconnected-(JP10-Pad2)") (class "Default")
      (node (ref "JP10") (pin "2") (pinfunction "2_2") (pintype "passive"))
    )
    (net (code "66") (name "unconnected-(JP10-Pad6)") (class "Default")
      (node (ref "JP10") (pin "6") (pinfunction "6_6") (pintype "passive"))
    )
    (net (code "67") (name "unconnected-(JP11-Pad1)") (class "Default")
      (node (ref "JP11") (pin "1") (pinfunction "1_1") (pintype "passive"))
    )
    (net (code "68") (name "unconnected-(JP11-Pad6)") (class "Default")
      (node (ref "JP11") (pin "6") (pinfunction "6_6") (pintype "passive"))
    )
    (net (code "69") (name "unconnected-(JP12-Pad3)") (class "Default")
      (node (ref "JP12") (pin "3") (pinfunction "3_3") (pintype "passive"))
    )
    (net (code "70") (name "unconnected-(JP12-Pad7)") (class "Default")
      (node (ref "JP12") (pin "7") (pinfunction "7_7") (pintype "passive"))
    )
    (net (code "71") (name "unconnected-(JP12-Pad8)") (class "Default")
      (node (ref "JP12") (pin "8") (pinfunction "8_8") (pintype "passive"))
    )
    (net (code "72") (name "unconnected-(U$4-Pad2)") (class "Default")
      (node (ref "U$4") (pin "2") (pinfunction "2_2") (pintype "passive"))
    )
    (net (code "73") (name "unconnected-(U$4-Pad4)") (class "Default")
      (node (ref "U$4") (pin "4") (pinfunction "4_4") (pintype "passive"))
    )
    (net (code "74") (name "unconnected-(U3-LINEIN-Pad48)") (class "Default")
      (node (ref "U3") (pin "48") (pinfunction "LINEIN_48") (pintype "bidirectional"))
    )
    (net (code "75") (name "unconnected-(U3-MICN-Pad2)") (class "Default")
      (node (ref "U3") (pin "2") (pinfunction "MICN_2") (pintype "bidirectional"))
    )
    (net (code "76") (name "unconnected-(U3-MICP-Pad1)") (class "Default")
      (node (ref "U3") (pin "1") (pinfunction "MICP_1") (pintype "bidirectional"))
    )
    (net (code "77") (name "unconnected-(U3-TX-Pad27)") (class "Default")
      (node (ref "U3") (pin "27") (pinfunction "TX_27") (pintype "bidirectional"))
    )
    (net (code "78") (name "unconnected-(U3-VCO-Pad15)") (class "Default")
      (node (ref "U3") (pin "15") (pinfunction "VCO_15") (pintype "bidirectional"))
    )
    (net (code "79") (name "unconnected-(U6-NC-Pad1)") (class "Default")
      (node (ref "U6") (pin "1") (pinfunction "NC_1") (pintype "bidirectional"))
    )
    (net (code "80") (name "unconnected-(U6-RSV-Pad8)") (class "Default")
      (node (ref "U6") (pin "8") (pinfunction "RSV_8") (pintype "bidirectional"))
    )
  )
)
